# ESP_Xung.net
KiCad netlist of a schematic drawn in Altium Designer
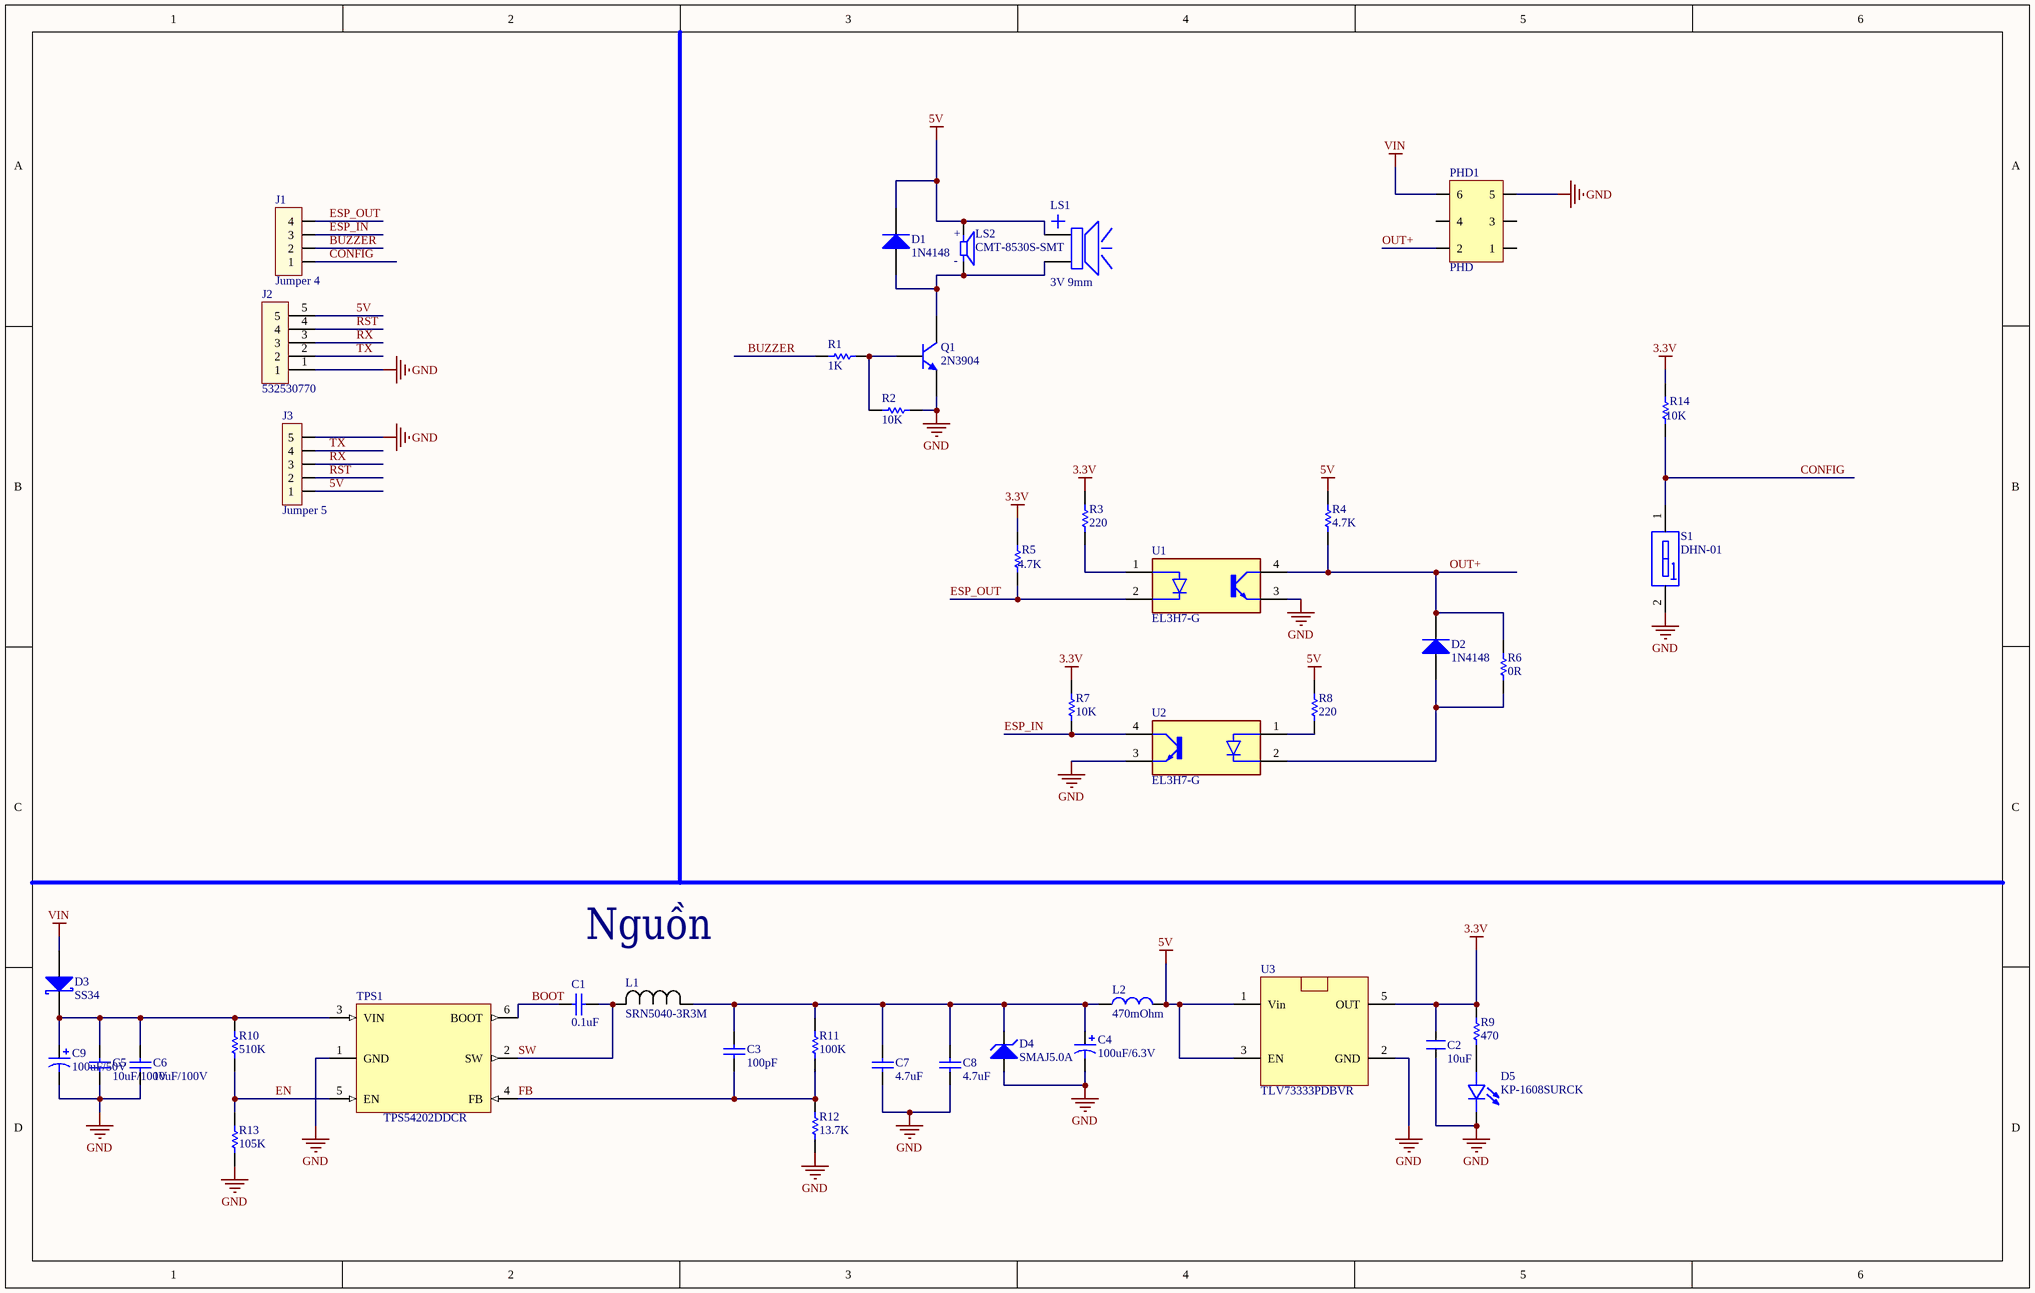
[diagram p0: ESP_Xung.SchDoc]

(export (version "E")
  (design (tool "Eeschema 10.0.6"))
  (components
    (comp (ref "C1")
      (value "0.1uF")
      (footprint "0603 - C")
      (description "CAP CER 1000PF 50V C0G/NP0 0603")
      (fields (field (name "MPN") "CL10C102JB8NNNC") (field (name "MFR") "SAMSUNG"))
      (libsource (lib "Library_Chip1") (part "Cap 0603 1nF"))
    )
    (comp (ref "C2")
      (value "10uF")
      (footprint "SM-0805")
      (description "Cap SMD")
      (libsource (lib "syhaunguyen") (part "CM"))
    )
    (comp (ref "C3")
      (value "100pF")
      (footprint "0603 - C")
      (description "CAP CER 1000PF 50V C0G/NP0 0603")
      (fields (field (name "MPN") "CL10C102JB8NNNC") (field (name "MFR") "SAMSUNG"))
      (libsource (lib "Library_Chip1") (part "Cap 0603 1nF"))
    )
    (comp (ref "C4")
      (value "100uF/6.3V")
      (footprint "3528 - TANTALUM")
      (description "CAP TANT 100UF 6.3V 10% 1411")
      (fields (field (name "MPN") "T491B107K006AT") (field (name "MFR") "Kemet"))
      (libsource (lib "Library_Chip") (part "Cap Tan 3528 100uF/6.3V"))
    )
    (comp (ref "C5")
      (value "10uF/100V")
      (footprint "1210 - C")
      (description "CAP CER 10UF 100V X7S 1210")
      (fields (field (name "MFR") "Murata Electronics") (field (name "MPN") "GRM32EC72A106KE05L"))
      (libsource (lib "Library_Chip") (part "Cap 1210 10uF"))
    )
    (comp (ref "C6")
      (value "10uF/100V")
      (footprint "1210 - C")
      (description "CAP CER 10UF 100V X7S 1210")
      (fields (field (name "MFR") "Murata Electronics") (field (name "MPN") "GRM32EC72A106KE05L"))
      (libsource (lib "Library_Chip") (part "Cap 1210 10uF"))
    )
    (comp (ref "C7")
      (value "C0603: 4.7uF")
      (footprint "0603 - C")
      (description "CAP CER 4.7UF 6.3V X5R 0603")
      (fields
        (field (name "MFR") "Taiyo Yuden")
        (field (name "MPN") "JMK107BJ475KA-T")
        (field (name "SIZE") "4.7uF")
      )
      (libsource (lib "Library_Chip1") (part "Cap 0603 4.7uF"))
    )
    (comp (ref "C8")
      (value "C0603: 4.7uF")
      (footprint "0603 - C")
      (description "CAP CER 4.7UF 6.3V X5R 0603")
      (fields
        (field (name "MFR") "Taiyo Yuden")
        (field (name "MPN") "JMK107BJ475KA-T")
        (field (name "SIZE") "4.7uF")
      )
      (libsource (lib "Library_Chip1") (part "Cap 0603 4.7uF"))
    )
    (comp (ref "C9")
      (value "100uF/50V")
      (footprint "CAP-ALU-SMD 8x11.7x3.1")
      (description "CAP ALUM 100UF 20% 50V SMD")
      (fields (field (name "MPN") "UWT1H101MNL1GS") (field (name "MFR") "Nichicon"))
      (libsource (lib "Library_Chip") (part "Cap Alu 100uF/50V"))
    )
    (comp (ref "D1")
      (value "1N4148")
      (footprint "SOD-123")
      (description "DIODE GEN PURP 100V 300MA SOD123")
      (fields (field (name "MPN") "1N4148W-7-F") (field (name "MFR") "DIODES"))
      (libsource (lib "Library_Chip1") (part "Diode 1N4148"))
    )
    (comp (ref "D2")
      (value "1N4148")
      (footprint "SOD-123")
      (description "DIODE GEN PURP 100V 300MA SOD123")
      (fields (field (name "MPN") "1N4148W-7-F") (field (name "MFR") "DIODES"))
      (libsource (lib "Library_Chip1") (part "Diode 1N4148"))
    )
    (comp (ref "D3")
      (value "SS34")
      (footprint "SOD-123")
      (description "DIODE SCHOTTKY 40V 3A SMA")
      (fields (field (name "MPN") "NRVBA340T3G") (field (name "MFR") "ON Semiconductor"))
      (libsource (lib "Library_Chip") (part "Diode SS34"))
    )
    (comp (ref "D4")
      (value "SMAJ5.0A")
      (footprint "Diode - SMA")
      (description "TVS DIODE 5VWM 9.2VC SMA")
      (fields (field (name "MFR") "Littelfuse Inc."))
      (libsource (lib "Library_Chip1") (part "Diode SMAJ5.0A"))
    )
    (comp (ref "D5")
      (value "KP-1608SURCK")
      (footprint "LED_KP-1608SURCK")
      (description "LED; SMD; 0603; red; 50-150mcd; 1.6x0.8mm; 120Â°; 20mA;")
      (fields (field (name "MF") "Kingbright"))
      (libsource (lib "Led_0603") (part "KP-1608SURCK"))
    )
    (comp (ref "J1")
      (value "Jumper 4")
      (footprint "JP4")
      (description "Jumper 4, 2.54mmx4")
      (libsource (lib "Library_ Connector") (part "JP4"))
    )
    (comp (ref "J2")
      (value "532530770")
      (footprint "MOLEX_532530770")
      (libsource (lib "5pin_2.0") (part "532530770"))
    )
    (comp (ref "J3")
      (value "Jumper 5")
      (footprint "JP5 - 1")
      (description "Jumper 5, 2.54mmx5")
      (libsource (lib "Library_ Connector") (part "JP5"))
    )
    (comp (ref "L1")
      (value "SRN5040-3R3M")
      (footprint "IND_SRN5040_BRN")
      (description "No Description Available")
      (libsource (lib "SRN5040-3R3M") (part "SRN5040-3R3M"))
    )
    (comp (ref "L2")
      (value "470mOhm")
      (footprint "0603 - L")
      (description "FERRITE BEAD 470 OHM 0603 1LN")
      (fields (field (name "MPN") "BLM18PG471SN1D"))
      (libsource (lib "Library_Chip") (part "Inductor 0603 470mOhm"))
    )
    (comp (ref "LS1")
      (value "3V 9mm")
      (footprint "Buzzer")
      (description "Buzzer 9*6mm (D*h)")
      (fields (field (name "MFR") "China") (field (name "MPN") "TMB09A03"))
      (libsource (lib "Library_Chip") (part "Speaker"))
    )
    (comp (ref "LS2")
      (value "CMT-8530S-SMT")
      (footprint "CUI_CMT-8530S-SMT")
      (fields (field (name "MF") "CUI DEVICES"))
      (libsource (lib "CMT-8530S-SMT") (part "CMT-8530S-SMT"))
    )
    (comp (ref "PHD1")
      (value "PHD")
      (footprint "PHD 2.0 2x3")
      (libsource (lib "Integrated_Library1") (part "Component_1"))
    )
    (comp (ref "Q1")
      (value "2N3904")
      (footprint "Library_Chip1:SOT23B")
      (description "TRANS NPN 40V 0.2A SOT-23")
      (fields (field (name "MPN") "MMBT3904") (field (name "MFR") "Fairchild"))
      (libsource (lib "Library_Chip1") (part "Transistor 2N3904"))
    )
    (comp (ref "R1")
      (value "1K")
      (footprint "0603 - R")
      (description "RES SMD 1K OHM 1% 1/10W 0603")
      (fields (field (name "MFR") "Yageo") (field (name "MPN") "RC0603FR-071KL"))
      (libsource (lib "Library_Chip") (part "Res 0603 1K"))
    )
    (comp (ref "R2")
      (value "10K")
      (footprint "0603 - R")
      (description "RES SMD 1K OHM 1% 1/10W 0603")
      (fields (field (name "MFR") "Yageo") (field (name "MPN") "RC0603FR-071KL"))
      (libsource (lib "Library_Chip") (part "Res 0603 1K"))
    )
    (comp (ref "R3")
      (value "220")
      (footprint "0603 - R")
      (description "RES SMD 1K OHM 1% 1/10W 0603")
      (fields (field (name "MFR") "Yageo") (field (name "MPN") "RC0603FR-071KL"))
      (libsource (lib "Library_Chip") (part "Res 0603 1K"))
    )
    (comp (ref "R4")
      (value "4.7K")
      (footprint "0603 - R")
      (description "RES SMD 1K OHM 1% 1/10W 0603")
      (fields (field (name "MFR") "Yageo") (field (name "MPN") "RC0603FR-071KL"))
      (libsource (lib "Library_Chip") (part "Res 0603 1K"))
    )
    (comp (ref "R5")
      (value "4.7K")
      (footprint "0603 - R")
      (description "RES SMD 1K OHM 1% 1/10W 0603")
      (fields (field (name "MFR") "Yageo") (field (name "MPN") "RC0603FR-071KL"))
      (libsource (lib "Library_Chip") (part "Res 0603 1K"))
    )
    (comp (ref "R6")
      (value "0R")
      (footprint "0603 - R")
      (description "RES SMD 1K OHM 1% 1/10W 0603")
      (fields (field (name "MFR") "Yageo") (field (name "MPN") "RC0603FR-071KL"))
      (libsource (lib "Library_Chip") (part "Res 0603 1K"))
    )
    (comp (ref "R7")
      (value "10K")
      (footprint "0603 - R")
      (description "RES SMD 1K OHM 1% 1/10W 0603")
      (fields (field (name "MFR") "Yageo") (field (name "MPN") "RC0603FR-071KL"))
      (libsource (lib "Library_Chip") (part "Res 0603 1K"))
    )
    (comp (ref "R8")
      (value "220")
      (footprint "0603 - R")
      (description "RES SMD 1K OHM 1% 1/10W 0603")
      (fields (field (name "MFR") "Yageo") (field (name "MPN") "RC0603FR-071KL"))
      (libsource (lib "Library_Chip") (part "Res 0603 1K"))
    )
    (comp (ref "R9")
      (value "470")
      (footprint "0603 - R")
      (description "RES SMD 1K OHM 1% 1/10W 0603")
      (fields (field (name "MFR") "Yageo") (field (name "MPN") "RC0603FR-071KL"))
      (libsource (lib "Library_Chip") (part "Res 0603 1K"))
    )
    (comp (ref "R10")
      (value "510K")
      (footprint "0603 - R")
      (description "RES SMD 1K OHM 1% 1/10W 0603")
      (fields (field (name "MFR") "Yageo") (field (name "MPN") "RC0603FR-071KL"))
      (libsource (lib "Library_Chip") (part "Res 0603 1K"))
    )
    (comp (ref "R11")
      (value "100K")
      (footprint "0603 - R")
      (description "RES SMD 1K OHM 1% 1/10W 0603")
      (fields (field (name "MFR") "Yageo") (field (name "MPN") "RC0603FR-071KL"))
      (libsource (lib "Library_Chip") (part "Res 0603 1K"))
    )
    (comp (ref "R12")
      (value "13.7K")
      (footprint "0603 - R")
      (description "RES SMD 1K OHM 1% 1/10W 0603")
      (fields (field (name "MFR") "Yageo") (field (name "MPN") "RC0603FR-071KL"))
      (libsource (lib "Library_Chip") (part "Res 0603 1K"))
    )
    (comp (ref "R13")
      (value "105K")
      (footprint "0603 - R")
      (description "RES SMD 1K OHM 1% 1/10W 0603")
      (fields (field (name "MFR") "Yageo") (field (name "MPN") "RC0603FR-071KL"))
      (libsource (lib "Library_Chip") (part "Res 0603 1K"))
    )
    (comp (ref "R14")
      (value "10K")
      (footprint "0603 - R")
      (description "RES SMD 1K OHM 1% 1/10W 0603")
      (fields (field (name "MFR") "Yageo") (field (name "MPN") "RC0603FR-071KL"))
      (libsource (lib "Library_Chip") (part "Res 0603 1K"))
    )
    (comp (ref "S1")
      (value "DHN-01")
      (footprint "DSHP01TSGDER")
      (description "Switch 1Bit")
      (fields (field (name "MFR") "kingtek-switch") (field (name "MPN") "DSHP01TSGER"))
      (libsource (lib "Library_Chip") (part "SW_DSHP01"))
    )
    (comp (ref "TPS1")
      (value "TPS54202DDCR")
      (footprint "SOT95P280X110-6N")
      (fields
        (field (name "MF") "Texas Instruments")
        (field (name "BUYPART") "https://www.snapeda.com/parts/TPS54202DDCR/Texas%20Instruments/view-part/565860/?ref=eda")
      )
      (libsource (lib "TPS54202DDCR") (part "TPS54202DDCR"))
    )
    (comp (ref "U1")
      (value "EL3H7-G")
      (footprint "SOIC127P700X200-4N")
      (description "Optoisolator Transistor Output 3750Vrms 1 Channel 4-SSOP")
      (fields (field (name "MF") "Everlight Electronics"))
      (libsource (lib "") (part "EL3H7-G_1"))
    )
    (comp (ref "U2")
      (value "EL3H7-G")
      (footprint "SOIC127P700X200-4N")
      (description "Optoisolator Transistor Output 3750Vrms 1 Channel 4-SSOP")
      (fields (field (name "MF") "Everlight Electronics"))
      (libsource (lib "EL3H7-G") (part "EL3H7-G"))
    )
    (comp (ref "U3")
      (value "TLV73333PDBVR")
      (footprint "SOT23-5")
      (description "IC REG LINEAR 3.3V 300MA SOT23-5")
      (fields (field (name "MFR") "TI"))
      (libsource (lib "Library_IC") (part "TLV73333PDBVR"))
    )
  )
  (nets
    (net (code "1") (name "/BOOT") (class "Default")
      (node (ref "C1") (pin "2") (pinfunction "2_2") (pintype "passive"))
      (node (ref "TPS1") (pin "6") (pinfunction "BOOT_6") (pintype "output"))
    )
    (net (code "2") (name "/BUZZER") (class "Default")
      (node (ref "J1") (pin "2") (pinfunction "2_2") (pintype "passive"))
      (node (ref "R1") (pin "1") (pinfunction "1_1") (pintype "passive"))
    )
    (net (code "3") (name "/CONFIG") (class "Default")
      (node (ref "J1") (pin "1") (pinfunction "1_1") (pintype "passive"))
      (node (ref "R14") (pin "1") (pinfunction "1_1") (pintype "passive"))
      (node (ref "S1") (pin "1") (pinfunction "A1_1") (pintype "passive"))
    )
    (net (code "4") (name "/EN") (class "Default")
      (node (ref "R10") (pin "2") (pinfunction "2_2") (pintype "passive"))
      (node (ref "R13") (pin "1") (pinfunction "1_1") (pintype "passive"))
      (node (ref "TPS1") (pin "5") (pinfunction "EN_5") (pintype "input"))
    )
    (net (code "5") (name "/ESP_IN") (class "Default")
      (node (ref "J1") (pin "3") (pinfunction "3_3") (pintype "passive"))
      (node (ref "R7") (pin "2") (pinfunction "2_2") (pintype "passive"))
      (node (ref "U2") (pin "4") (pinfunction "CO_4") (pintype "passive"))
    )
    (net (code "6") (name "/ESP_OUT") (class "Default")
      (node (ref "J1") (pin "4") (pinfunction "4_4") (pintype "passive"))
      (node (ref "R5") (pin "1") (pinfunction "1_1") (pintype "passive"))
      (node (ref "U1") (pin "2") (pinfunction "C_2") (pintype "passive"))
    )
    (net (code "7") (name "/FB") (class "Default")
      (node (ref "C3") (pin "2") (pinfunction "2_2") (pintype "passive"))
      (node (ref "R11") (pin "2") (pinfunction "2_2") (pintype "passive"))
      (node (ref "R12") (pin "1") (pinfunction "1_1") (pintype "passive"))
      (node (ref "TPS1") (pin "4") (pinfunction "FB_4") (pintype "input"))
    )
    (net (code "8") (name "/OUT+") (class "Default")
      (node (ref "D2") (pin "2") (pinfunction "K_2") (pintype "passive"))
      (node (ref "PHD1") (pin "1") (pinfunction "2_1") (pintype "passive"))
      (node (ref "R4") (pin "2") (pinfunction "2_2") (pintype "passive"))
      (node (ref "R6") (pin "1") (pinfunction "1_1") (pintype "passive"))
      (node (ref "U1") (pin "4") (pinfunction "CO_4") (pintype "passive"))
    )
    (net (code "9") (name "/RST") (class "Default")
      (node (ref "J2") (pin "4") (pinfunction "4_4") (pintype "passive"))
      (node (ref "J3") (pin "2") (pinfunction "2_2") (pintype "passive"))
    )
    (net (code "10") (name "/RX") (class "Default")
      (node (ref "J2") (pin "3") (pinfunction "3_3") (pintype "passive"))
      (node (ref "J3") (pin "3") (pinfunction "3_3") (pintype "passive"))
    )
    (net (code "11") (name "/SW") (class "Default")
      (node (ref "C1") (pin "1") (pinfunction "1_1") (pintype "passive"))
      (node (ref "L1") (pin "2") (pinfunction "2_2") (pintype "passive"))
      (node (ref "TPS1") (pin "2") (pinfunction "SW_2") (pintype "output"))
    )
    (net (code "12") (name "/TX") (class "Default")
      (node (ref "J2") (pin "2") (pinfunction "2_2") (pintype "passive"))
      (node (ref "J3") (pin "4") (pinfunction "4_4") (pintype "passive"))
    )
    (net (code "13") (name "3.3V") (class "Default")
      (node (ref "C2") (pin "2") (pinfunction "2_2") (pintype "passive"))
      (node (ref "R14") (pin "2") (pinfunction "2_2") (pintype "passive"))
      (node (ref "R3") (pin "1") (pinfunction "1_1") (pintype "passive"))
      (node (ref "R5") (pin "2") (pinfunction "2_2") (pintype "passive"))
      (node (ref "R7") (pin "1") (pinfunction "1_1") (pintype "passive"))
      (node (ref "R9") (pin "1") (pinfunction "1_1") (pintype "passive"))
      (node (ref "U3") (pin "5") (pinfunction "OUT_5") (pintype "passive"))
    )
    (net (code "14") (name "5V") (class "Default")
      (node (ref "D1") (pin "2") (pinfunction "K_2") (pintype "passive"))
      (node (ref "J2") (pin "5") (pinfunction "5_5") (pintype "passive"))
      (node (ref "J3") (pin "1") (pinfunction "1_1") (pintype "passive"))
      (node (ref "L2") (pin "2") (pinfunction "2_2") (pintype "passive"))
      (node (ref "LS1") (pin "1") (pinfunction "1_1") (pintype "passive"))
      (node (ref "LS2") (pin "P") (pinfunction "P_P") (pintype "passive"))
      (node (ref "R4") (pin "1") (pinfunction "1_1") (pintype "passive"))
      (node (ref "R8") (pin "1") (pinfunction "1_1") (pintype "passive"))
      (node (ref "U3") (pin "1") (pinfunction "Vin_1") (pintype "passive"))
      (node (ref "U3") (pin "3") (pinfunction "EN_3") (pintype "passive"))
    )
    (net (code "15") (name "GND") (class "Default")
      (node (ref "C2") (pin "1") (pinfunction "1_1") (pintype "passive"))
      (node (ref "C4") (pin "2") (pinfunction "2_2") (pintype "passive"))
      (node (ref "C5") (pin "1") (pinfunction "1_1") (pintype "passive"))
      (node (ref "C6") (pin "2") (pinfunction "2_2") (pintype "passive"))
      (node (ref "C7") (pin "1") (pinfunction "1_1") (pintype "passive"))
      (node (ref "C8") (pin "1") (pinfunction "1_1") (pintype "passive"))
      (node (ref "C9") (pin "2") (pinfunction "2_2") (pintype "passive"))
      (node (ref "D4") (pin "1") (pinfunction "A_1") (pintype "passive"))
      (node (ref "D5") (pin "2") (pinfunction "C_2") (pintype "passive"))
      (node (ref "J2") (pin "1") (pinfunction "1_1") (pintype "passive"))
      (node (ref "J3") (pin "5") (pinfunction "5_5") (pintype "passive"))
      (node (ref "PHD1") (pin "4") (pinfunction "5_4") (pintype "passive"))
      (node (ref "Q1") (pin "2") (pinfunction "E_2") (pintype "passive"))
      (node (ref "R12") (pin "2") (pinfunction "2_2") (pintype "passive"))
      (node (ref "R13") (pin "2") (pinfunction "2_2") (pintype "passive"))
      (node (ref "R2") (pin "2") (pinfunction "2_2") (pintype "passive"))
      (node (ref "S1") (pin "2") (pinfunction "A2_2") (pintype "passive"))
      (node (ref "TPS1") (pin "1") (pinfunction "GND_1") (pintype "power_in"))
      (node (ref "U1") (pin "3") (pinfunction "E_3") (pintype "passive"))
      (node (ref "U2") (pin "3") (pinfunction "E_3") (pintype "passive"))
      (node (ref "U3") (pin "2") (pinfunction "GND_2") (pintype "passive"))
    )
    (net (code "16") (name "Net-(D1-A)") (class "Default")
      (node (ref "D1") (pin "1") (pinfunction "A_1") (pintype "passive"))
      (node (ref "LS1") (pin "2") (pinfunction "2_2") (pintype "passive"))
      (node (ref "LS2") (pin "N") (pinfunction "N_N") (pintype "passive"))
      (node (ref "Q1") (pin "3") (pinfunction "C_3") (pintype "passive"))
    )
    (net (code "17") (name "Net-(D2-A)") (class "Default")
      (node (ref "D2") (pin "1") (pinfunction "A_1") (pintype "passive"))
      (node (ref "R6") (pin "2") (pinfunction "2_2") (pintype "passive"))
      (node (ref "U2") (pin "2") (pinfunction "C_2") (pintype "passive"))
    )
    (net (code "18") (name "Net-(D3-K)") (class "Default")
      (node (ref "C5") (pin "2") (pinfunction "2_2") (pintype "passive"))
      (node (ref "C6") (pin "1") (pinfunction "1_1") (pintype "passive"))
      (node (ref "C9") (pin "1") (pinfunction "1_1") (pintype "passive"))
      (node (ref "D3") (pin "2") (pinfunction "K_2") (pintype "passive"))
      (node (ref "R10") (pin "1") (pinfunction "1_1") (pintype "passive"))
      (node (ref "TPS1") (pin "3") (pinfunction "VIN_3") (pintype "input"))
    )
    (net (code "19") (name "Net-(D4-K)") (class "Default")
      (node (ref "C3") (pin "1") (pinfunction "1_1") (pintype "passive"))
      (node (ref "C4") (pin "1") (pinfunction "1_1") (pintype "passive"))
      (node (ref "C7") (pin "2") (pinfunction "2_2") (pintype "passive"))
      (node (ref "C8") (pin "2") (pinfunction "2_2") (pintype "passive"))
      (node (ref "D4") (pin "2") (pinfunction "K_2") (pintype "passive"))
      (node (ref "L1") (pin "1") (pinfunction "1_1") (pintype "passive"))
      (node (ref "L2") (pin "1") (pinfunction "1_1") (pintype "passive"))
      (node (ref "R11") (pin "1") (pinfunction "1_1") (pintype "passive"))
    )
    (net (code "20") (name "Net-(D5-A)") (class "Default")
      (node (ref "D5") (pin "1") (pinfunction "A_1") (pintype "passive"))
      (node (ref "R9") (pin "2") (pinfunction "2_2") (pintype "passive"))
    )
    (net (code "21") (name "Net-(Q1-B)") (class "Default")
      (node (ref "Q1") (pin "1") (pinfunction "B_1") (pintype "passive"))
      (node (ref "R1") (pin "2") (pinfunction "2_2") (pintype "passive"))
      (node (ref "R2") (pin "1") (pinfunction "1_1") (pintype "passive"))
    )
    (net (code "22") (name "Net-(U1-A)") (class "Default")
      (node (ref "R3") (pin "2") (pinfunction "2_2") (pintype "passive"))
      (node (ref "U1") (pin "1") (pinfunction "A_1") (pintype "passive"))
    )
    (net (code "23") (name "Net-(U2-A)") (class "Default")
      (node (ref "R8") (pin "2") (pinfunction "2_2") (pintype "passive"))
      (node (ref "U2") (pin "1") (pinfunction "A_1") (pintype "passive"))
    )
    (net (code "24") (name "VIN") (class "Default")
      (node (ref "D3") (pin "1") (pinfunction "A_1") (pintype "passive"))
      (node (ref "PHD1") (pin "5") (pinfunction "6_5") (pintype "passive"))
    )
    (net (code "25") (name "unconnected-(PHD1-3-Pad2)") (class "Default")
      (node (ref "PHD1") (pin "2") (pinfunction "3_2") (pintype "passive"))
    )
    (net (code "26") (name "unconnected-(PHD1-4-Pad3)") (class "Default")
      (node (ref "PHD1") (pin "3") (pinfunction "4_3") (pintype "passive"))
    )
    (net (code "27") (name "unconnected-(PHD1-Pad1)") (class "Default")
      (node (ref "PHD1") (pin "1") (pinfunction "1_1") (pintype "passive"))
    )
    (net (code "28") (name "unconnected-(U3-NC-Pad4)") (class "Default")
      (node (ref "U3") (pin "4") (pinfunction "NC_4") (pintype "passive"))
    )
  )
)
